# ScanMasterVCI.net
KiCad netlist of a schematic drawn in EAGLE
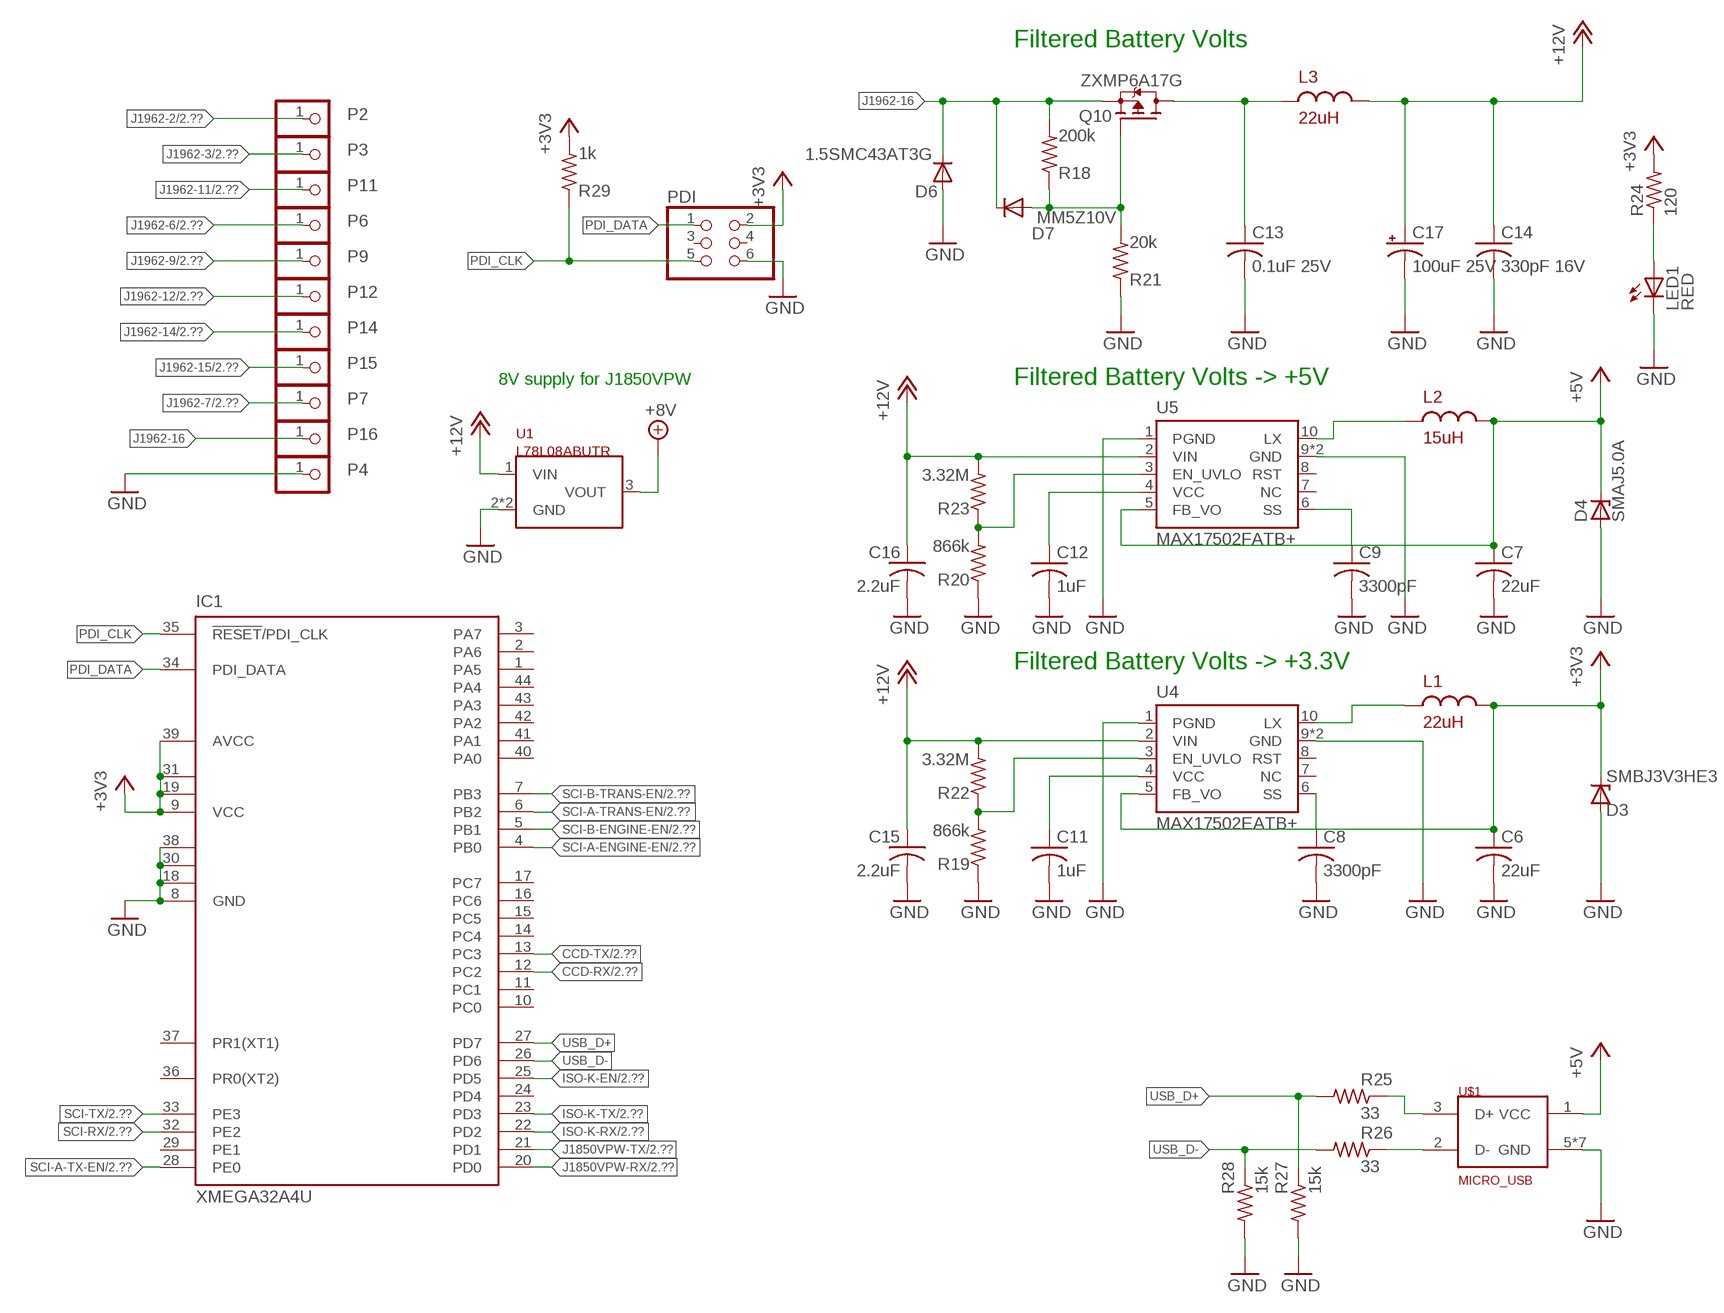
[diagram p0: schematic, sheet 1]
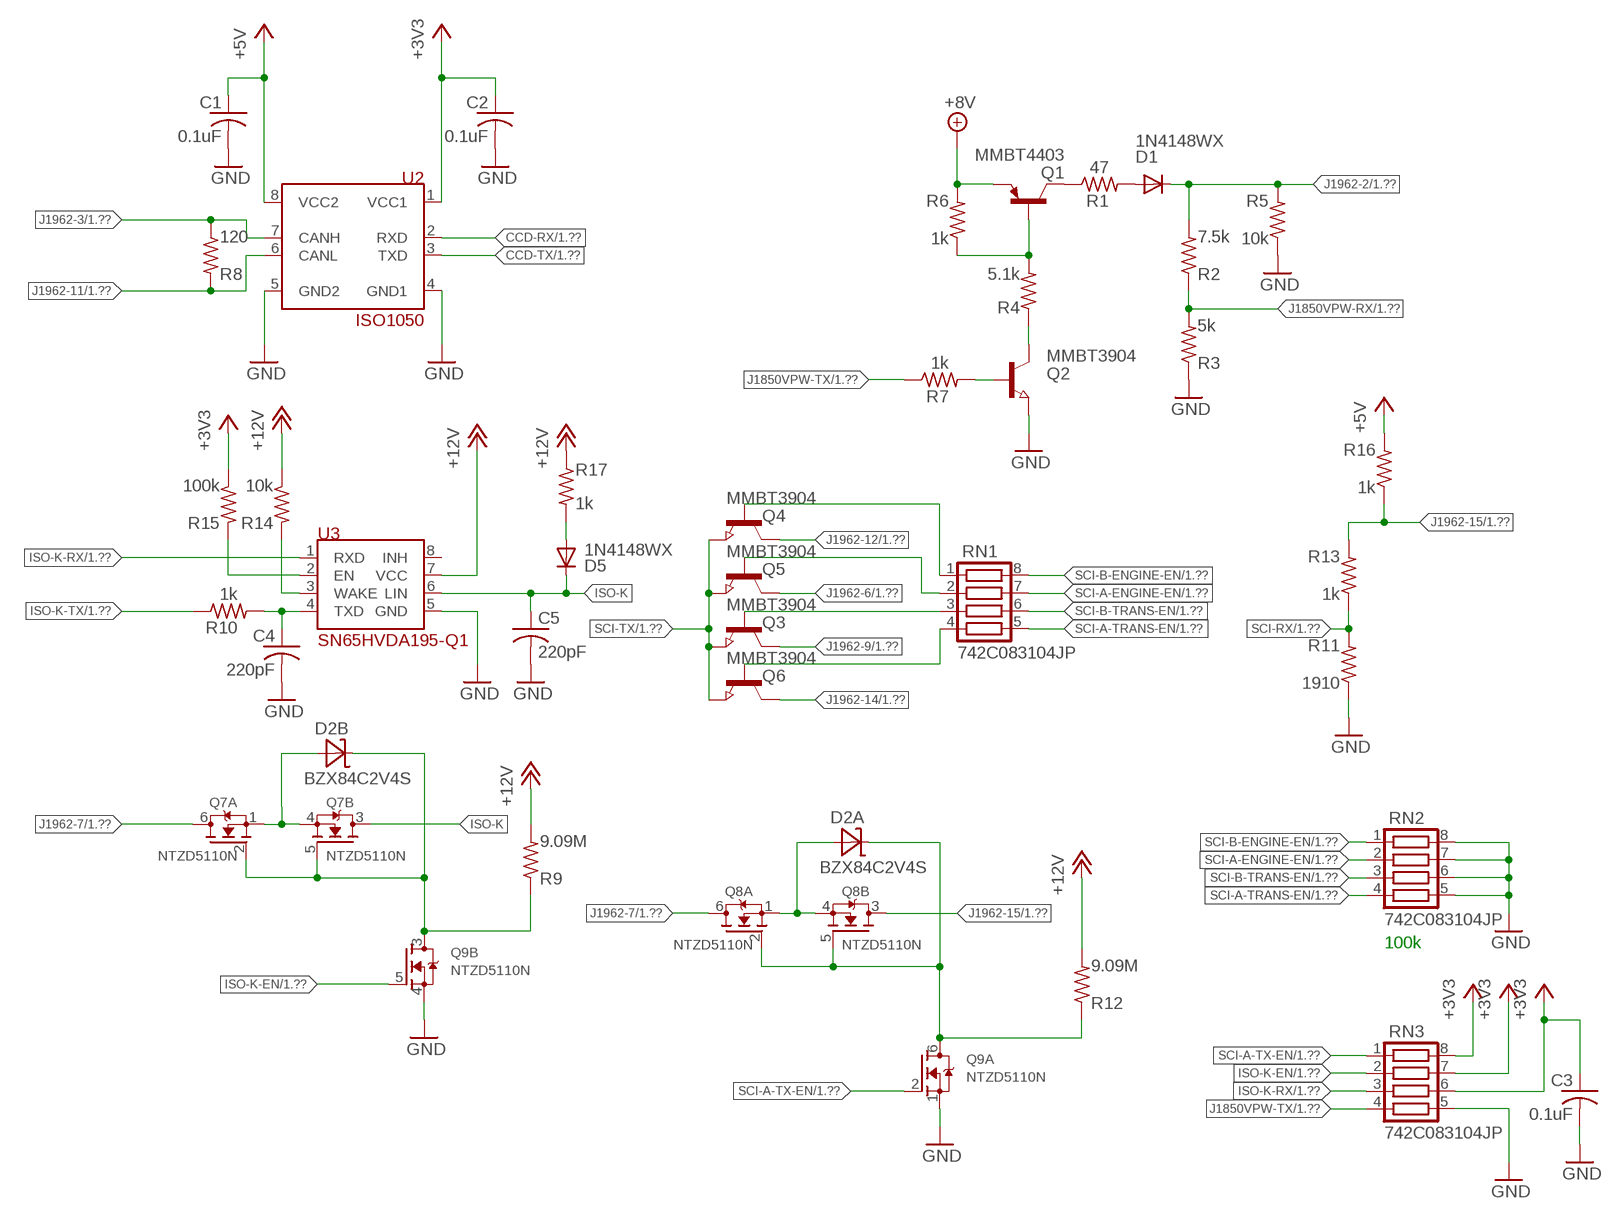
[diagram p1: schematic, sheet 2]

(export (version "E")
  (design (tool "Eeschema 10.0.6"))
  (components
    (comp (ref "C6")
      (value "22uF")
      (footprint "eagle-import:C0603")
      (libsource (lib "eagle-import") (part "C-USC0603"))
    )
    (comp (ref "C7")
      (value "22uF")
      (footprint "eagle-import:C0603")
      (libsource (lib "eagle-import") (part "C-USC0603"))
    )
    (comp (ref "C8")
      (value "3300pF")
      (footprint "eagle-import:C0603")
      (libsource (lib "eagle-import") (part "C-USC0603"))
    )
    (comp (ref "C9")
      (value "3300pF")
      (footprint "eagle-import:C0603")
      (libsource (lib "eagle-import") (part "C-USC0603"))
    )
    (comp (ref "C11")
      (value "1uF")
      (footprint "eagle-import:C0603")
      (libsource (lib "eagle-import") (part "C-USC0603"))
    )
    (comp (ref "C12")
      (value "1uF")
      (footprint "eagle-import:C0603")
      (libsource (lib "eagle-import") (part "C-USC0603"))
    )
    (comp (ref "C13")
      (value "0.1uF 25V")
      (footprint "eagle-import:C0603")
      (libsource (lib "eagle-import") (part "C-USC0603"))
    )
    (comp (ref "C14")
      (value "330pF 16V")
      (footprint "eagle-import:C0603")
      (libsource (lib "eagle-import") (part "C-USC0603"))
    )
    (comp (ref "C15")
      (value "2.2uF")
      (footprint "eagle-import:C0603")
      (libsource (lib "eagle-import") (part "C-USC0603"))
    )
    (comp (ref "C16")
      (value "2.2uF")
      (footprint "eagle-import:C0603")
      (libsource (lib "eagle-import") (part "C-USC0603"))
    )
    (comp (ref "C17")
      (value "100uF 25V")
      (footprint "eagle-import:CPOL-RADIAL-2.5MM-6.5MM")
      (libsource (lib "eagle-import") (part "100UF-POLAR-RADIAL-2.5MM-25V-20%"))
    )
    (comp (ref "D3")
      (value "SMBJ3V3HE3")
      (footprint "eagle-import:SMB")
      (libsource (lib "eagle-import") (part "ZENER-DIODESMB"))
    )
    (comp (ref "D4")
      (value "SMAJ5.0A")
      (footprint "eagle-import:SMB")
      (libsource (lib "eagle-import") (part "ZENER-DIODESMB"))
    )
    (comp (ref "D6")
      (value "1.5SMC43AT3G")
      (footprint "eagle-import:SMC")
      (libsource (lib "eagle-import") (part "DIODE-SMC"))
    )
    (comp (ref "D7")
      (value "MM5Z10V")
      (footprint "eagle-import:SOD523")
      (libsource (lib "eagle-import") (part "DIODE-SOD523"))
    )
    (comp (ref "IC1")
      (value "XMEGA32A4U")
      (footprint "eagle-import:TQFP44")
      (libsource (lib "eagle-import") (part "XMEGA16A4A"))
    )
    (comp (ref "L1")
      (value "22uH")
      (footprint "eagle-import:L0603")
      (libsource (lib "eagle-import") (part "INDUCTOR"))
    )
    (comp (ref "L2")
      (value "15uH")
      (footprint "eagle-import:L0603")
      (libsource (lib "eagle-import") (part "INDUCTOR"))
    )
    (comp (ref "L3")
      (value "22uH")
      (footprint "eagle-import:L0603")
      (libsource (lib "eagle-import") (part "INDUCTOR"))
    )
    (comp (ref "LED1")
      (value "RED")
      (footprint "eagle-import:CHIP-LED0603")
      (libsource (lib "eagle-import") (part "LEDCHIP-LED0603"))
    )
    (comp (ref "P2")
      (value "PINHD-1X1")
      (footprint "eagle-import:1X01")
      (libsource (lib "eagle-import") (part "PINHD-1X1"))
    )
    (comp (ref "P3")
      (value "PINHD-1X1")
      (footprint "eagle-import:1X01")
      (libsource (lib "eagle-import") (part "PINHD-1X1"))
    )
    (comp (ref "P4")
      (value "PINHD-1X1")
      (footprint "eagle-import:1X01")
      (libsource (lib "eagle-import") (part "PINHD-1X1"))
    )
    (comp (ref "P6")
      (value "PINHD-1X1")
      (footprint "eagle-import:1X01")
      (libsource (lib "eagle-import") (part "PINHD-1X1"))
    )
    (comp (ref "P7")
      (value "PINHD-1X1")
      (footprint "eagle-import:1X01")
      (libsource (lib "eagle-import") (part "PINHD-1X1"))
    )
    (comp (ref "P9")
      (value "PINHD-1X1")
      (footprint "eagle-import:1X01")
      (libsource (lib "eagle-import") (part "PINHD-1X1"))
    )
    (comp (ref "P11")
      (value "PINHD-1X1")
      (footprint "eagle-import:1X01")
      (libsource (lib "eagle-import") (part "PINHD-1X1"))
    )
    (comp (ref "P12")
      (value "PINHD-1X1")
      (footprint "eagle-import:1X01")
      (libsource (lib "eagle-import") (part "PINHD-1X1"))
    )
    (comp (ref "P14")
      (value "PINHD-1X1")
      (footprint "eagle-import:1X01")
      (libsource (lib "eagle-import") (part "PINHD-1X1"))
    )
    (comp (ref "P15")
      (value "PINHD-1X1")
      (footprint "eagle-import:1X01")
      (libsource (lib "eagle-import") (part "PINHD-1X1"))
    )
    (comp (ref "P16")
      (value "PINHD-1X1")
      (footprint "eagle-import:1X01")
      (libsource (lib "eagle-import") (part "PINHD-1X1"))
    )
    (comp (ref "PDI")
      (value "PINHD-2X3")
      (footprint "eagle-import:2X03")
      (libsource (lib "eagle-import") (part "PINHD-2X3"))
    )
    (comp (ref "Q10")
      (value "ZXMP6A17G")
      (footprint "eagle-import:SOT223")
      (libsource (lib "eagle-import") (part "ZXMP6A17G"))
    )
    (comp (ref "R18")
      (value "200k")
      (footprint "eagle-import:R0603")
      (libsource (lib "eagle-import") (part "R-US_R0603"))
    )
    (comp (ref "R19")
      (value "866k")
      (footprint "eagle-import:R0603")
      (libsource (lib "eagle-import") (part "R-US_R0603"))
    )
    (comp (ref "R20")
      (value "866k")
      (footprint "eagle-import:R0603")
      (libsource (lib "eagle-import") (part "R-US_R0603"))
    )
    (comp (ref "R21")
      (value "20k")
      (footprint "eagle-import:R0603")
      (libsource (lib "eagle-import") (part "R-US_R0603"))
    )
    (comp (ref "R22")
      (value "3.32M")
      (footprint "eagle-import:R0603")
      (libsource (lib "eagle-import") (part "R-US_R0603"))
    )
    (comp (ref "R23")
      (value "3.32M")
      (footprint "eagle-import:R0603")
      (libsource (lib "eagle-import") (part "R-US_R0603"))
    )
    (comp (ref "R24")
      (value "120")
      (footprint "eagle-import:R0603")
      (libsource (lib "eagle-import") (part "resistor_348_R-US_R0603"))
    )
    (comp (ref "R25")
      (value "33")
      (footprint "eagle-import:R0603")
      (libsource (lib "eagle-import") (part "R-US_R0603"))
    )
    (comp (ref "R26")
      (value "33")
      (footprint "eagle-import:R0603")
      (libsource (lib "eagle-import") (part "R-US_R0603"))
    )
    (comp (ref "R27")
      (value "15k")
      (footprint "eagle-import:R0603")
      (libsource (lib "eagle-import") (part "R-US_R0603"))
    )
    (comp (ref "R28")
      (value "15k")
      (footprint "eagle-import:R0603")
      (libsource (lib "eagle-import") (part "R-US_R0603"))
    )
    (comp (ref "R29")
      (value "1k")
      (footprint "eagle-import:R0603")
      (libsource (lib "eagle-import") (part "R-US_R0603"))
    )
    (comp (ref "U$1")
      (value "MICRO_USB")
      (footprint "eagle-import:10118192")
      (libsource (lib "eagle-import") (part "MICRO_USB"))
    )
    (comp (ref "U1")
      (value "L78L08ABUTR")
      (footprint "eagle-import:SOT89")
      (libsource (lib "eagle-import") (part "L78L"))
    )
    (comp (ref "U4")
      (value "MAX17502EATB+")
      (footprint "eagle-import:TDFN-10-EP")
      (libsource (lib "eagle-import") (part "MAX17502"))
    )
    (comp (ref "U5")
      (value "MAX17502FATB+")
      (footprint "eagle-import:TDFN-10-EP")
      (libsource (lib "eagle-import") (part "MAX17502"))
    )
    (comp (ref "C1")
      (value "0.1uF")
      (footprint "eagle-import:C0603")
      (libsource (lib "eagle-import") (part "C-USC0603"))
    )
    (comp (ref "C2")
      (value "0.1uF")
      (footprint "eagle-import:C0603")
      (libsource (lib "eagle-import") (part "C-USC0603"))
    )
    (comp (ref "C3")
      (value "0.1uF")
      (footprint "eagle-import:C0603")
      (libsource (lib "eagle-import") (part "C-USC0603"))
    )
    (comp (ref "C4")
      (value "220pF")
      (footprint "eagle-import:C0603")
      (libsource (lib "eagle-import") (part "C-USC0603"))
    )
    (comp (ref "C5")
      (value "220pF")
      (footprint "eagle-import:C0603")
      (libsource (lib "eagle-import") (part "C-USC0603"))
    )
    (comp (ref "D1")
      (value "1N4148WX")
      (footprint "eagle-import:SOD323-R")
      (libsource (lib "eagle-import") (part "DIODE-SOD323-R"))
    )
    (comp (ref "D2")
      (value "BZX84C2V4S")
      (footprint "eagle-import:SOT363")
      (libsource (lib "eagle-import") (part "BZX84C2V4S"))
    )
    (comp (ref "D5")
      (value "1N4148WX")
      (footprint "eagle-import:SOD323-R")
      (libsource (lib "eagle-import") (part "DIODE-SOD323-R"))
    )
    (comp (ref "Q1")
      (value "MMBT4403")
      (footprint "eagle-import:SOT23-BEC")
      (libsource (lib "eagle-import") (part "MMBT4403SMDLT1"))
    )
    (comp (ref "Q2")
      (value "MMBT3904")
      (footprint "eagle-import:SOT23")
      (libsource (lib "eagle-import") (part "NPN-TRANSISTOR_SOT23"))
    )
    (comp (ref "Q3")
      (value "MMBT3904")
      (footprint "eagle-import:SOT23")
      (libsource (lib "eagle-import") (part "NPN-TRANSISTOR_SOT23"))
    )
    (comp (ref "Q4")
      (value "MMBT3904")
      (footprint "eagle-import:SOT23")
      (libsource (lib "eagle-import") (part "NPN-TRANSISTOR_SOT23"))
    )
    (comp (ref "Q5")
      (value "MMBT3904")
      (footprint "eagle-import:SOT23")
      (libsource (lib "eagle-import") (part "NPN-TRANSISTOR_SOT23"))
    )
    (comp (ref "Q6")
      (value "MMBT3904")
      (footprint "eagle-import:SOT23")
      (libsource (lib "eagle-import") (part "NPN-TRANSISTOR_SOT23"))
    )
    (comp (ref "Q7")
      (value "NTZD5110N")
      (footprint "eagle-import:SOT563")
      (libsource (lib "eagle-import") (part "NTZD5110N"))
    )
    (comp (ref "Q8")
      (value "NTZD5110N")
      (footprint "eagle-import:SOT563")
      (libsource (lib "eagle-import") (part "NTZD5110N"))
    )
    (comp (ref "Q9")
      (value "NTZD5110N")
      (footprint "eagle-import:SOT563")
      (libsource (lib "eagle-import") (part "NTZD5110N"))
    )
    (comp (ref "R1")
      (value "47")
      (footprint "eagle-import:R0603")
      (libsource (lib "eagle-import") (part "R-US_R0603"))
    )
    (comp (ref "R2")
      (value "7.5k")
      (footprint "eagle-import:R0603")
      (libsource (lib "eagle-import") (part "R-US_R0603"))
    )
    (comp (ref "R3")
      (value "5k")
      (footprint "eagle-import:R0603")
      (libsource (lib "eagle-import") (part "R-US_R0603"))
    )
    (comp (ref "R4")
      (value "5.1k")
      (footprint "eagle-import:R0603")
      (libsource (lib "eagle-import") (part "R-US_R0603"))
    )
    (comp (ref "R5")
      (value "10k")
      (footprint "eagle-import:R0603")
      (libsource (lib "eagle-import") (part "R-US_R0603"))
    )
    (comp (ref "R6")
      (value "1k")
      (footprint "eagle-import:R0603")
      (libsource (lib "eagle-import") (part "R-US_R0603"))
    )
    (comp (ref "R7")
      (value "1k")
      (footprint "eagle-import:R0603")
      (libsource (lib "eagle-import") (part "R-US_R0603"))
    )
    (comp (ref "R8")
      (value "120")
      (footprint "eagle-import:R0603")
      (libsource (lib "eagle-import") (part "R-US_R0603"))
    )
    (comp (ref "R9")
      (value "9.09M")
      (footprint "eagle-import:R0603")
      (libsource (lib "eagle-import") (part "R-US_R0603"))
    )
    (comp (ref "R10")
      (value "1k")
      (footprint "eagle-import:R0603")
      (libsource (lib "eagle-import") (part "R-US_R0603"))
    )
    (comp (ref "R11")
      (value "1910")
      (footprint "eagle-import:R0603")
      (libsource (lib "eagle-import") (part "R-US_R0603"))
    )
    (comp (ref "R12")
      (value "9.09M")
      (footprint "eagle-import:R0603")
      (libsource (lib "eagle-import") (part "R-US_R0603"))
    )
    (comp (ref "R13")
      (value "1k")
      (footprint "eagle-import:R0603")
      (libsource (lib "eagle-import") (part "R-US_R0603"))
    )
    (comp (ref "R14")
      (value "10k")
      (footprint "eagle-import:R0603")
      (libsource (lib "eagle-import") (part "R-US_R0603"))
    )
    (comp (ref "R15")
      (value "100k")
      (footprint "eagle-import:R0603")
      (libsource (lib "eagle-import") (part "R-US_R0603"))
    )
    (comp (ref "R16")
      (value "1k")
      (footprint "eagle-import:R0603")
      (libsource (lib "eagle-import") (part "R-US_R0603"))
    )
    (comp (ref "R17")
      (value "1k")
      (footprint "eagle-import:R0603")
      (libsource (lib "eagle-import") (part "R-US_R0603"))
    )
    (comp (ref "RN1")
      (value "742C083104JP")
      (footprint "eagle-import:CTS742C083")
      (libsource (lib "eagle-import") (part "CTS742C083"))
    )
    (comp (ref "RN2")
      (value "742C083104JP")
      (footprint "eagle-import:CTS742C083")
      (libsource (lib "eagle-import") (part "CTS742C083"))
    )
    (comp (ref "RN3")
      (value "742C083104JP")
      (footprint "eagle-import:CTS742C083")
      (libsource (lib "eagle-import") (part "CTS742C083"))
    )
    (comp (ref "U2")
      (value "ISO1050")
      (footprint "eagle-import:SOP08")
      (libsource (lib "eagle-import") (part "ISO1050"))
    )
    (comp (ref "U3")
      (value "SN65HVDA195-Q1")
      (footprint "eagle-import:SO08")
      (libsource (lib "eagle-import") (part "SN65HVDA195-Q1"))
    )
  )
  (nets
    (net (code "1") (name "+3V3") (class "Default")
      (node (ref "C2") (pin "1") (pinfunction "1_1") (pintype "passive"))
      (node (ref "C3") (pin "1") (pinfunction "1_1") (pintype "passive"))
      (node (ref "C6") (pin "1") (pinfunction "1_1") (pintype "passive"))
      (node (ref "D3") (pin "C") (pinfunction "C_C") (pintype "passive"))
      (node (ref "IC1") (pin "19") (pinfunction "VCC1_19") (pintype "power_in"))
      (node (ref "IC1") (pin "31") (pinfunction "VCC2_31") (pintype "power_in"))
      (node (ref "IC1") (pin "39") (pinfunction "AVCC_39") (pintype "power_in"))
      (node (ref "IC1") (pin "9") (pinfunction "VCC_9") (pintype "power_in"))
      (node (ref "L1") (pin "2") (pinfunction "2_2") (pintype "passive"))
      (node (ref "PDI") (pin "2") (pinfunction "2_2") (pintype "passive"))
      (node (ref "R15") (pin "1") (pinfunction "1_1") (pintype "passive"))
      (node (ref "R24") (pin "2") (pinfunction "2_2") (pintype "passive"))
      (node (ref "R29") (pin "2") (pinfunction "2_2") (pintype "passive"))
      (node (ref "RN3") (pin "6") (pinfunction "6_6") (pintype "passive"))
      (node (ref "RN3") (pin "7") (pinfunction "7_7") (pintype "passive"))
      (node (ref "RN3") (pin "8") (pinfunction "8_8") (pintype "passive"))
      (node (ref "U2") (pin "1") (pinfunction "VCC1_1") (pintype "power_in"))
      (node (ref "U4") (pin "5") (pinfunction "FB_VO_5") (pintype "input"))
    )
    (net (code "2") (name "+5V") (class "Default")
      (node (ref "C1") (pin "1") (pinfunction "1_1") (pintype "passive"))
      (node (ref "C7") (pin "1") (pinfunction "1_1") (pintype "passive"))
      (node (ref "D4") (pin "C") (pinfunction "C_C") (pintype "passive"))
      (node (ref "L2") (pin "2") (pinfunction "2_2") (pintype "passive"))
      (node (ref "R16") (pin "2") (pinfunction "2_2") (pintype "passive"))
      (node (ref "U$1") (pin "1") (pinfunction "VCC_1") (pintype "power_in"))
      (node (ref "U2") (pin "8") (pinfunction "VCC2_8") (pintype "power_in"))
      (node (ref "U5") (pin "5") (pinfunction "FB_VO_5") (pintype "input"))
    )
    (net (code "3") (name "+8V") (class "Default")
      (node (ref "Q1") (pin "E") (pinfunction "E_E") (pintype "passive"))
      (node (ref "R6") (pin "2") (pinfunction "2_2") (pintype "passive"))
      (node (ref "U1") (pin "3") (pinfunction "VOUT_3") (pintype "power_in"))
    )
    (net (code "4") (name "+12V") (class "Default")
      (node (ref "C14") (pin "1") (pinfunction "1_1") (pintype "passive"))
      (node (ref "C15") (pin "1") (pinfunction "1_1") (pintype "passive"))
      (node (ref "C16") (pin "1") (pinfunction "1_1") (pintype "passive"))
      (node (ref "C17") (pin "1") (pinfunction "+_1") (pintype "passive"))
      (node (ref "L3") (pin "2") (pinfunction "2_2") (pintype "passive"))
      (node (ref "R12") (pin "2") (pinfunction "2_2") (pintype "passive"))
      (node (ref "R14") (pin "1") (pinfunction "1_1") (pintype "passive"))
      (node (ref "R17") (pin "1") (pinfunction "1_1") (pintype "passive"))
      (node (ref "R22") (pin "2") (pinfunction "2_2") (pintype "passive"))
      (node (ref "R23") (pin "2") (pinfunction "2_2") (pintype "passive"))
      (node (ref "R9") (pin "2") (pinfunction "2_2") (pintype "passive"))
      (node (ref "U1") (pin "1") (pinfunction "VIN_1") (pintype "power_in"))
      (node (ref "U3") (pin "7") (pinfunction "VCC_7") (pintype "power_in"))
      (node (ref "U4") (pin "2") (pinfunction "VIN_2") (pintype "power_in"))
      (node (ref "U5") (pin "2") (pinfunction "VIN_2") (pintype "power_in"))
    )
    (net (code "5") (name "CCD-RX") (class "Default")
      (node (ref "IC1") (pin "12") (pinfunction "PC2_12") (pintype "bidirectional"))
      (node (ref "U2") (pin "2") (pinfunction "RXD_2") (pintype "output"))
    )
    (net (code "6") (name "CCD-TX") (class "Default")
      (node (ref "IC1") (pin "13") (pinfunction "PC3_13") (pintype "bidirectional"))
      (node (ref "U2") (pin "3") (pinfunction "TXD_3") (pintype "input"))
    )
    (net (code "7") (name "GND") (class "Default")
      (node (ref "C1") (pin "2") (pinfunction "2_2") (pintype "passive"))
      (node (ref "C11") (pin "2") (pinfunction "2_2") (pintype "passive"))
      (node (ref "C12") (pin "2") (pinfunction "2_2") (pintype "passive"))
      (node (ref "C13") (pin "2") (pinfunction "2_2") (pintype "passive"))
      (node (ref "C14") (pin "2") (pinfunction "2_2") (pintype "passive"))
      (node (ref "C15") (pin "2") (pinfunction "2_2") (pintype "passive"))
      (node (ref "C16") (pin "2") (pinfunction "2_2") (pintype "passive"))
      (node (ref "C17") (pin "2") (pinfunction "-_2") (pintype "passive"))
      (node (ref "C2") (pin "2") (pinfunction "2_2") (pintype "passive"))
      (node (ref "C3") (pin "2") (pinfunction "2_2") (pintype "passive"))
      (node (ref "C4") (pin "2") (pinfunction "2_2") (pintype "passive"))
      (node (ref "C5") (pin "2") (pinfunction "2_2") (pintype "passive"))
      (node (ref "C6") (pin "2") (pinfunction "2_2") (pintype "passive"))
      (node (ref "C7") (pin "2") (pinfunction "2_2") (pintype "passive"))
      (node (ref "C8") (pin "2") (pinfunction "2_2") (pintype "passive"))
      (node (ref "C9") (pin "2") (pinfunction "2_2") (pintype "passive"))
      (node (ref "D3") (pin "A") (pinfunction "A_A") (pintype "passive"))
      (node (ref "D4") (pin "A") (pinfunction "A_A") (pintype "passive"))
      (node (ref "D6") (pin "A") (pinfunction "A_A") (pintype "passive"))
      (node (ref "IC1") (pin "18") (pinfunction "GND1_18") (pintype "power_in"))
      (node (ref "IC1") (pin "30") (pinfunction "GND2_30") (pintype "power_in"))
      (node (ref "IC1") (pin "38") (pinfunction "GND3_38") (pintype "power_in"))
      (node (ref "IC1") (pin "8") (pinfunction "GND_8") (pintype "power_in"))
      (node (ref "LED1") (pin "C") (pinfunction "C_C") (pintype "passive"))
      (node (ref "P4") (pin "1") (pinfunction "1_1") (pintype "passive"))
      (node (ref "PDI") (pin "6") (pinfunction "6_6") (pintype "passive"))
      (node (ref "Q2") (pin "2") (pinfunction "E_2") (pintype "passive"))
      (node (ref "Q9") (pin "1") (pinfunction "S_1") (pintype "passive"))
      (node (ref "Q9") (pin "4") (pinfunction "S_4") (pintype "passive"))
      (node (ref "R11") (pin "1") (pinfunction "1_1") (pintype "passive"))
      (node (ref "R19") (pin "1") (pinfunction "1_1") (pintype "passive"))
      (node (ref "R20") (pin "1") (pinfunction "1_1") (pintype "passive"))
      (node (ref "R21") (pin "1") (pinfunction "1_1") (pintype "passive"))
      (node (ref "R27") (pin "2") (pinfunction "2_2") (pintype "passive"))
      (node (ref "R28") (pin "2") (pinfunction "2_2") (pintype "passive"))
      (node (ref "R3") (pin "1") (pinfunction "1_1") (pintype "passive"))
      (node (ref "R5") (pin "1") (pinfunction "1_1") (pintype "passive"))
      (node (ref "RN2") (pin "5") (pinfunction "5_5") (pintype "passive"))
      (node (ref "RN2") (pin "6") (pinfunction "6_6") (pintype "passive"))
      (node (ref "RN2") (pin "7") (pinfunction "7_7") (pintype "passive"))
      (node (ref "RN2") (pin "8") (pinfunction "8_8") (pintype "passive"))
      (node (ref "RN3") (pin "5") (pinfunction "5_5") (pintype "passive"))
      (node (ref "U$1") (pin "5") (pinfunction "GND_5") (pintype "power_in"))
      (node (ref "U$1") (pin "M1") (pinfunction "GND_M1") (pintype "power_in"))
      (node (ref "U$1") (pin "M2") (pinfunction "GND_M2") (pintype "power_in"))
      (node (ref "U$1") (pin "M3") (pinfunction "GND_M3") (pintype "power_in"))
      (node (ref "U$1") (pin "M4") (pinfunction "GND_M4") (pintype "power_in"))
      (node (ref "U$1") (pin "M5") (pinfunction "GND_M5") (pintype "power_in"))
      (node (ref "U$1") (pin "M6") (pinfunction "GND_M6") (pintype "power_in"))
      (node (ref "U1") (pin "2") (pinfunction "GND_2") (pintype "power_in"))
      (node (ref "U1") (pin "2@1") (pinfunction "GND_2@1") (pintype "power_in"))
      (node (ref "U2") (pin "4") (pinfunction "GND1_4") (pintype "power_in"))
      (node (ref "U2") (pin "5") (pinfunction "GND2_5") (pintype "power_in"))
      (node (ref "U3") (pin "5") (pinfunction "GND_5") (pintype "power_in"))
      (node (ref "U4") (pin "1") (pinfunction "PGND_1") (pintype "power_in"))
      (node (ref "U4") (pin "9") (pinfunction "GND_9") (pintype "power_in"))
      (node (ref "U4") (pin "EPAD") (pinfunction "GND_EPAD") (pintype "power_in"))
      (node (ref "U5") (pin "1") (pinfunction "PGND_1") (pintype "power_in"))
      (node (ref "U5") (pin "9") (pinfunction "GND_9") (pintype "power_in"))
      (node (ref "U5") (pin "EPAD") (pinfunction "GND_EPAD") (pintype "power_in"))
    )
    (net (code "8") (name "ISO-K") (class "Default")
      (node (ref "C5") (pin "1") (pinfunction "1_1") (pintype "passive"))
      (node (ref "D5") (pin "C") (pinfunction "C_C") (pintype "passive"))
      (node (ref "Q7") (pin "3") (pinfunction "D_3") (pintype "passive"))
      (node (ref "U3") (pin "6") (pinfunction "LIN_6") (pintype "bidirectional"))
    )
    (net (code "9") (name "ISO-K-EN") (class "Default")
      (node (ref "IC1") (pin "25") (pinfunction "PD5_25") (pintype "bidirectional"))
      (node (ref "Q9") (pin "5") (pinfunction "G_5") (pintype "passive"))
      (node (ref "RN3") (pin "2") (pinfunction "2_2") (pintype "passive"))
    )
    (net (code "10") (name "ISO-K-RX") (class "Default")
      (node (ref "IC1") (pin "22") (pinfunction "PD2_22") (pintype "bidirectional"))
      (node (ref "RN3") (pin "3") (pinfunction "3_3") (pintype "passive"))
      (node (ref "U3") (pin "1") (pinfunction "RXD_1") (pintype "output"))
    )
    (net (code "11") (name "ISO-K-TX") (class "Default")
      (node (ref "IC1") (pin "23") (pinfunction "PD3_23") (pintype "bidirectional"))
      (node (ref "R10") (pin "1") (pinfunction "1_1") (pintype "passive"))
    )
    (net (code "12") (name "J1850VPW-RX") (class "Default")
      (node (ref "IC1") (pin "20") (pinfunction "PD0_20") (pintype "bidirectional"))
      (node (ref "R2") (pin "1") (pinfunction "1_1") (pintype "passive"))
      (node (ref "R3") (pin "2") (pinfunction "2_2") (pintype "passive"))
    )
    (net (code "13") (name "J1850VPW-TX") (class "Default")
      (node (ref "IC1") (pin "21") (pinfunction "PD1_21") (pintype "bidirectional"))
      (node (ref "R7") (pin "1") (pinfunction "1_1") (pintype "passive"))
      (node (ref "RN3") (pin "4") (pinfunction "4_4") (pintype "passive"))
    )
    (net (code "14") (name "J1962-2") (class "Default")
      (node (ref "D1") (pin "C") (pinfunction "C_C") (pintype "passive"))
      (node (ref "P2") (pin "1") (pinfunction "1_1") (pintype "passive"))
      (node (ref "R2") (pin "2") (pinfunction "2_2") (pintype "passive"))
      (node (ref "R5") (pin "2") (pinfunction "2_2") (pintype "passive"))
    )
    (net (code "15") (name "J1962-3") (class "Default")
      (node (ref "P3") (pin "1") (pinfunction "1_1") (pintype "passive"))
      (node (ref "R8") (pin "1") (pinfunction "1_1") (pintype "passive"))
      (node (ref "U2") (pin "7") (pinfunction "CANH_7") (pintype "input"))
    )
    (net (code "16") (name "J1962-6") (class "Default")
      (node (ref "P6") (pin "1") (pinfunction "1_1") (pintype "passive"))
      (node (ref "Q5") (pin "3") (pinfunction "C_3") (pintype "passive"))
    )
    (net (code "17") (name "J1962-7") (class "Default")
      (node (ref "P7") (pin "1") (pinfunction "1_1") (pintype "passive"))
      (node (ref "Q7") (pin "6") (pinfunction "D_6") (pintype "passive"))
      (node (ref "Q8") (pin "6") (pinfunction "D_6") (pintype "passive"))
    )
    (net (code "18") (name "J1962-9") (class "Default")
      (node (ref "P9") (pin "1") (pinfunction "1_1") (pintype "passive"))
      (node (ref "Q3") (pin "3") (pinfunction "C_3") (pintype "passive"))
    )
    (net (code "19") (name "J1962-11") (class "Default")
      (node (ref "P11") (pin "1") (pinfunction "1_1") (pintype "passive"))
      (node (ref "R8") (pin "2") (pinfunction "2_2") (pintype "passive"))
      (node (ref "U2") (pin "6") (pinfunction "CANL_6") (pintype "input"))
    )
    (net (code "20") (name "J1962-12") (class "Default")
      (node (ref "P12") (pin "1") (pinfunction "1_1") (pintype "passive"))
      (node (ref "Q4") (pin "3") (pinfunction "C_3") (pintype "passive"))
    )
    (net (code "21") (name "J1962-14") (class "Default")
      (node (ref "P14") (pin "1") (pinfunction "1_1") (pintype "passive"))
      (node (ref "Q6") (pin "3") (pinfunction "C_3") (pintype "passive"))
    )
    (net (code "22") (name "J1962-15") (class "Default")
      (node (ref "P15") (pin "1") (pinfunction "1_1") (pintype "passive"))
      (node (ref "Q8") (pin "3") (pinfunction "D_3") (pintype "passive"))
      (node (ref "R13") (pin "2") (pinfunction "2_2") (pintype "passive"))
      (node (ref "R16") (pin "1") (pinfunction "1_1") (pintype "passive"))
    )
    (net (code "23") (name "J1962-16") (class "Default")
      (node (ref "D6") (pin "C") (pinfunction "C_C") (pintype "passive"))
      (node (ref "D7") (pin "C") (pinfunction "C_C") (pintype "passive"))
      (node (ref "P16") (pin "1") (pinfunction "1_1") (pintype "passive"))
      (node (ref "Q10") (pin "3") (pinfunction "S_3") (pintype "passive"))
      (node (ref "R18") (pin "2") (pinfunction "2_2") (pintype "passive"))
    )
    (net (code "24") (name "Net-(C13-Pad1)") (class "Default")
      (node (ref "C13") (pin "1") (pinfunction "1_1") (pintype "passive"))
      (node (ref "L3") (pin "1") (pinfunction "1_1") (pintype "passive"))
      (node (ref "Q10") (pin "2") (pinfunction "D_2") (pintype "passive"))
      (node (ref "Q10") (pin "4") (pinfunction "D_4") (pintype "passive"))
    )
    (net (code "25") (name "Net-(D1-PadA)") (class "Default")
      (node (ref "D1") (pin "A") (pinfunction "A_A") (pintype "passive"))
      (node (ref "R1") (pin "2") (pinfunction "2_2") (pintype "passive"))
    )
    (net (code "26") (name "Net-(D2A-A)") (class "Default")
      (node (ref "D2") (pin "2") (pinfunction "A_2") (pintype "passive"))
      (node (ref "Q8") (pin "1") (pinfunction "S_1") (pintype "passive"))
      (node (ref "Q8") (pin "4") (pinfunction "S_4") (pintype "passive"))
    )
    (net (code "27") (name "Net-(D2A-C)") (class "Default")
      (node (ref "D2") (pin "3") (pinfunction "C_3") (pintype "passive"))
      (node (ref "Q8") (pin "2") (pinfunction "G_2") (pintype "passive"))
      (node (ref "Q8") (pin "5") (pinfunction "G_5") (pintype "passive"))
      (node (ref "Q9") (pin "6") (pinfunction "D_6") (pintype "passive"))
      (node (ref "R12") (pin "1") (pinfunction "1_1") (pintype "passive"))
    )
    (net (code "28") (name "Net-(D2B-A)") (class "Default")
      (node (ref "D2") (pin "5") (pinfunction "A_5") (pintype "passive"))
      (node (ref "Q7") (pin "1") (pinfunction "S_1") (pintype "passive"))
      (node (ref "Q7") (pin "4") (pinfunction "S_4") (pintype "passive"))
    )
    (net (code "29") (name "Net-(D2B-C)") (class "Default")
      (node (ref "D2") (pin "6") (pinfunction "C_6") (pintype "passive"))
      (node (ref "Q7") (pin "2") (pinfunction "G_2") (pintype "passive"))
      (node (ref "Q7") (pin "5") (pinfunction "G_5") (pintype "passive"))
      (node (ref "Q9") (pin "3") (pinfunction "D_3") (pintype "passive"))
      (node (ref "R9") (pin "1") (pinfunction "1_1") (pintype "passive"))
    )
    (net (code "30") (name "Net-(D5-PadA)") (class "Default")
      (node (ref "D5") (pin "A") (pinfunction "A_A") (pintype "passive"))
      (node (ref "R17") (pin "2") (pinfunction "2_2") (pintype "passive"))
    )
    (net (code "31") (name "Net-(LED1-PadA)") (class "Default")
      (node (ref "LED1") (pin "A") (pinfunction "A_A") (pintype "passive"))
      (node (ref "R24") (pin "1") (pinfunction "1_1") (pintype "passive"))
    )
    (net (code "32") (name "Net-(Q1-PadB)") (class "Default")
      (node (ref "Q1") (pin "B") (pinfunction "B_B") (pintype "passive"))
      (node (ref "R4") (pin "2") (pinfunction "2_2") (pintype "passive"))
      (node (ref "R6") (pin "1") (pinfunction "1_1") (pintype "passive"))
    )
    (net (code "33") (name "Net-(Q1-PadC)") (class "Default")
      (node (ref "Q1") (pin "C") (pinfunction "C_C") (pintype "passive"))
      (node (ref "R1") (pin "1") (pinfunction "1_1") (pintype "passive"))
    )
    (net (code "34") (name "Net-(Q2-B)") (class "Default")
      (node (ref "Q2") (pin "1") (pinfunction "B_1") (pintype "passive"))
      (node (ref "R7") (pin "2") (pinfunction "2_2") (pintype "passive"))
    )
    (net (code "35") (name "Net-(Q2-C)") (class "Default")
      (node (ref "Q2") (pin "3") (pinfunction "C_3") (pintype "passive"))
      (node (ref "R4") (pin "1") (pinfunction "1_1") (pintype "passive"))
    )
    (net (code "36") (name "Net-(Q3-B)") (class "Default")
      (node (ref "Q3") (pin "1") (pinfunction "B_1") (pintype "passive"))
      (node (ref "RN1") (pin "3") (pinfunction "3_3") (pintype "passive"))
    )
    (net (code "37") (name "Net-(Q4-B)") (class "Default")
      (node (ref "Q4") (pin "1") (pinfunction "B_1") (pintype "passive"))
      (node (ref "RN1") (pin "1") (pinfunction "1_1") (pintype "passive"))
    )
    (net (code "38") (name "Net-(Q5-B)") (class "Default")
      (node (ref "Q5") (pin "1") (pinfunction "B_1") (pintype "passive"))
      (node (ref "RN1") (pin "2") (pinfunction "2_2") (pintype "passive"))
    )
    (net (code "39") (name "Net-(Q6-B)") (class "Default")
      (node (ref "Q6") (pin "1") (pinfunction "B_1") (pintype "passive"))
      (node (ref "RN1") (pin "4") (pinfunction "4_4") (pintype "passive"))
    )
    (net (code "40") (name "Net-(Q10-G)") (class "Default")
      (node (ref "D7") (pin "A") (pinfunction "A_A") (pintype "passive"))
      (node (ref "Q10") (pin "1") (pinfunction "G_1") (pintype "passive"))
      (node (ref "R18") (pin "1") (pinfunction "1_1") (pintype "passive"))
      (node (ref "R21") (pin "2") (pinfunction "2_2") (pintype "passive"))
    )
    (net (code "41") (name "Net-(U$1-D+)") (class "Default")
      (node (ref "R25") (pin "1") (pinfunction "1_1") (pintype "passive"))
      (node (ref "U$1") (pin "3") (pinfunction "D+_3") (pintype "bidirectional"))
    )
    (net (code "42") (name "Net-(U$1-D-)") (class "Default")
      (node (ref "R26") (pin "1") (pinfunction "1_1") (pintype "passive"))
      (node (ref "U$1") (pin "2") (pinfunction "D-_2") (pintype "bidirectional"))
    )
    (net (code "43") (name "Net-(U3-EN)") (class "Default")
      (node (ref "R15") (pin "2") (pinfunction "2_2") (pintype "passive"))
      (node (ref "U3") (pin "2") (pinfunction "EN_2") (pintype "input"))
    )
    (net (code "44") (name "Net-(U3-TXD)") (class "Default")
      (node (ref "C4") (pin "1") (pinfunction "1_1") (pintype "passive"))
      (node (ref "R10") (pin "2") (pinfunction "2_2") (pintype "passive"))
      (node (ref "U3") (pin "4") (pinfunction "TXD_4") (pintype "input"))
    )
    (net (code "45") (name "Net-(U3-WAKE)") (class "Default")
      (node (ref "R14") (pin "2") (pinfunction "2_2") (pintype "passive"))
      (node (ref "U3") (pin "3") (pinfunction "WAKE_3") (pintype "input"))
    )
    (net (code "46") (name "Net-(U4-EN_UVLO)") (class "Default")
      (node (ref "R19") (pin "2") (pinfunction "2_2") (pintype "passive"))
      (node (ref "R22") (pin "1") (pinfunction "1_1") (pintype "passive"))
      (node (ref "U4") (pin "3") (pinfunction "EN_UVLO_3") (pintype "input"))
    )
    (net (code "47") (name "Net-(U4-LX)") (class "Default")
      (node (ref "L1") (pin "1") (pinfunction "1_1") (pintype "passive"))
      (node (ref "U4") (pin "10") (pinfunction "LX_10") (pintype "power_in"))
    )
    (net (code "48") (name "Net-(U4-SS)") (class "Default")
      (node (ref "C8") (pin "1") (pinfunction "1_1") (pintype "passive"))
      (node (ref "U4") (pin "6") (pinfunction "SS_6") (pintype "input"))
    )
    (net (code "49") (name "Net-(U4-VCC)") (class "Default")
      (node (ref "C11") (pin "1") (pinfunction "1_1") (pintype "passive"))
      (node (ref "U4") (pin "4") (pinfunction "VCC_4") (pintype "power_in"))
    )
    (net (code "50") (name "Net-(U5-EN_UVLO)") (class "Default")
      (node (ref "R20") (pin "2") (pinfunction "2_2") (pintype "passive"))
      (node (ref "R23") (pin "1") (pinfunction "1_1") (pintype "passive"))
      (node (ref "U5") (pin "3") (pinfunction "EN_UVLO_3") (pintype "input"))
    )
    (net (code "51") (name "Net-(U5-LX)") (class "Default")
      (node (ref "L2") (pin "1") (pinfunction "1_1") (pintype "passive"))
      (node (ref "U5") (pin "10") (pinfunction "LX_10") (pintype "power_in"))
    )
    (net (code "52") (name "Net-(U5-SS)") (class "Default")
      (node (ref "C9") (pin "1") (pinfunction "1_1") (pintype "passive"))
      (node (ref "U5") (pin "6") (pinfunction "SS_6") (pintype "input"))
    )
    (net (code "53") (name "Net-(U5-VCC)") (class "Default")
      (node (ref "C12") (pin "1") (pinfunction "1_1") (pintype "passive"))
      (node (ref "U5") (pin "4") (pinfunction "VCC_4") (pintype "power_in"))
    )
    (net (code "54") (name "PDI_CLK") (class "Default")
      (node (ref "IC1") (pin "35") (pinfunction "~{RESET}/PDI_CLK_35") (pintype "bidirectional"))
      (node (ref "PDI") (pin "5") (pinfunction "5_5") (pintype "passive"))
      (node (ref "R29") (pin "1") (pinfunction "1_1") (pintype "passive"))
    )
    (net (code "55") (name "PDI_DATA") (class "Default")
      (node (ref "IC1") (pin "34") (pinfunction "PDI_DATA_34") (pintype "bidirectional"))
      (node (ref "PDI") (pin "1") (pinfunction "1_1") (pintype "passive"))
    )
    (net (code "56") (name "SCI-A-ENGINE-EN") (class "Default")
      (node (ref "IC1") (pin "4") (pinfunction "PB0_4") (pintype "bidirectional"))
      (node (ref "RN1") (pin "7") (pinfunction "7_7") (pintype "passive"))
      (node (ref "RN2") (pin "2") (pinfunction "2_2") (pintype "passive"))
    )
    (net (code "57") (name "SCI-A-TRANS-EN") (class "Default")
      (node (ref "IC1") (pin "6") (pinfunction "PB2_6") (pintype "bidirectional"))
      (node (ref "RN1") (pin "5") (pinfunction "5_5") (pintype "passive"))
      (node (ref "RN2") (pin "4") (pinfunction "4_4") (pintype "passive"))
    )
    (net (code "58") (name "SCI-A-TX-EN") (class "Default")
      (node (ref "IC1") (pin "28") (pinfunction "PE0_28") (pintype "bidirectional"))
      (node (ref "Q9") (pin "2") (pinfunction "G_2") (pintype "passive"))
      (node (ref "RN3") (pin "1") (pinfunction "1_1") (pintype "passive"))
    )
    (net (code "59") (name "SCI-B-ENGINE-EN") (class "Default")
      (node (ref "IC1") (pin "5") (pinfunction "PB1_5") (pintype "bidirectional"))
      (node (ref "RN1") (pin "8") (pinfunction "8_8") (pintype "passive"))
      (node (ref "RN2") (pin "1") (pinfunction "1_1") (pintype "passive"))
    )
    (net (code "60") (name "SCI-B-TRANS-EN") (class "Default")
      (node (ref "IC1") (pin "7") (pinfunction "PB3_7") (pintype "bidirectional"))
      (node (ref "RN1") (pin "6") (pinfunction "6_6") (pintype "passive"))
      (node (ref "RN2") (pin "3") (pinfunction "3_3") (pintype "passive"))
    )
    (net (code "61") (name "SCI-RX") (class "Default")
      (node (ref "IC1") (pin "32") (pinfunction "PE2_32") (pintype "bidirectional"))
      (node (ref "R11") (pin "2") (pinfunction "2_2") (pintype "passive"))
      (node (ref "R13") (pin "1") (pinfunction "1_1") (pintype "passive"))
    )
    (net (code "62") (name "SCI-TX") (class "Default")
      (node (ref "IC1") (pin "33") (pinfunction "PE3_33") (pintype "bidirectional"))
      (node (ref "Q3") (pin "2") (pinfunction "E_2") (pintype "passive"))
      (node (ref "Q4") (pin "2") (pinfunction "E_2") (pintype "passive"))
      (node (ref "Q5") (pin "2") (pinfunction "E_2") (pintype "passive"))
      (node (ref "Q6") (pin "2") (pinfunction "E_2") (pintype "passive"))
    )
    (net (code "63") (name "USB_D+") (class "Default")
      (node (ref "IC1") (pin "27") (pinfunction "PD7_27") (pintype "bidirectional"))
      (node (ref "R25") (pin "2") (pinfunction "2_2") (pintype "passive"))
      (node (ref "R27") (pin "1") (pinfunction "1_1") (pintype "passive"))
    )
    (net (code "64") (name "USB_D-") (class "Default")
      (node (ref "IC1") (pin "26") (pinfunction "PD6_26") (pintype "bidirectional"))
      (node (ref "R26") (pin "2") (pinfunction "2_2") (pintype "passive"))
      (node (ref "R28") (pin "1") (pinfunction "1_1") (pintype "passive"))
    )
    (net (code "65") (name "unconnected-(IC1-PA0-Pad40)") (class "Default")
      (node (ref "IC1") (pin "40") (pinfunction "PA0_40") (pintype "bidirectional"))
    )
    (net (code "66") (name "unconnected-(IC1-PA1-Pad41)") (class "Default")
      (node (ref "IC1") (pin "41") (pinfunction "PA1_41") (pintype "bidirectional"))
    )
    (net (code "67") (name "unconnected-(IC1-PA2-Pad42)") (class "Default")
      (node (ref "IC1") (pin "42") (pinfunction "PA2_42") (pintype "bidirectional"))
    )
    (net (code "68") (name "unconnected-(IC1-PA3-Pad43)") (class "Default")
      (node (ref "IC1") (pin "43") (pinfunction "PA3_43") (pintype "bidirectional"))
    )
    (net (code "69") (name "unconnected-(IC1-PA4-Pad44)") (class "Default")
      (node (ref "IC1") (pin "44") (pinfunction "PA4_44") (pintype "bidirectional"))
    )
    (net (code "70") (name "unconnected-(IC1-PA5-Pad1)") (class "Default")
      (node (ref "IC1") (pin "1") (pinfunction "PA5_1") (pintype "bidirectional"))
    )
    (net (code "71") (name "unconnected-(IC1-PA6-Pad2)") (class "Default")
      (node (ref "IC1") (pin "2") (pinfunction "PA6_2") (pintype "bidirectional"))
    )
    (net (code "72") (name "unconnected-(IC1-PA7-Pad3)") (class "Default")
      (node (ref "IC1") (pin "3") (pinfunction "PA7_3") (pintype "bidirectional"))
    )
    (net (code "73") (name "unconnected-(IC1-PC0-Pad10)") (class "Default")
      (node (ref "IC1") (pin "10") (pinfunction "PC0_10") (pintype "bidirectional"))
    )
    (net (code "74") (name "unconnected-(IC1-PC1-Pad11)") (class "Default")
      (node (ref "IC1") (pin "11") (pinfunction "PC1_11") (pintype "bidirectional"))
    )
    (net (code "75") (name "unconnected-(IC1-PC4-Pad14)") (class "Default")
      (node (ref "IC1") (pin "14") (pinfunction "PC4_14") (pintype "bidirectional"))
    )
    (net (code "76") (name "unconnected-(IC1-PC5-Pad15)") (class "Default")
      (node (ref "IC1") (pin "15") (pinfunction "PC5_15") (pintype "bidirectional"))
    )
    (net (code "77") (name "unconnected-(IC1-PC6-Pad16)") (class "Default")
      (node (ref "IC1") (pin "16") (pinfunction "PC6_16") (pintype "bidirectional"))
    )
    (net (code "78") (name "unconnected-(IC1-PC7-Pad17)") (class "Default")
      (node (ref "IC1") (pin "17") (pinfunction "PC7_17") (pintype "bidirectional"))
    )
    (net (code "79") (name "unconnected-(IC1-PD4-Pad24)") (class "Default")
      (node (ref "IC1") (pin "24") (pinfunction "PD4_24") (pintype "bidirectional"))
    )
    (net (code "80") (name "unconnected-(IC1-PE1-Pad29)") (class "Default")
      (node (ref "IC1") (pin "29") (pinfunction "PE1_29") (pintype "bidirectional"))
    )
    (net (code "81") (name "unconnected-(IC1-PR0(XT2)-Pad36)") (class "Default")
      (node (ref "IC1") (pin "36") (pinfunction "PR0(XT2)_36") (pintype "bidirectional"))
    )
    (net (code "82") (name "unconnected-(IC1-PR1(XT1)-Pad37)") (class "Default")
      (node (ref "IC1") (pin "37") (pinfunction "PR1(XT1)_37") (pintype "bidirectional"))
    )
    (net (code "83") (name "unconnected-(PDI-Pad3)") (class "Default")
      (node (ref "PDI") (pin "3") (pinfunction "3_3") (pintype "passive"))
    )
    (net (code "84") (name "unconnected-(PDI-Pad4)") (class "Default")
      (node (ref "PDI") (pin "4") (pinfunction "4_4") (pintype "passive"))
    )
    (net (code "85") (name "unconnected-(U3-INH-Pad8)") (class "Default")
      (node (ref "U3") (pin "8") (pinfunction "INH_8") (pintype "output"))
    )
    (net (code "86") (name "unconnected-(U4-NC-Pad7)") (class "Default")
      (node (ref "U4") (pin "7") (pinfunction "NC_7") (pintype "no_connect"))
    )
    (net (code "87") (name "unconnected-(U4-RST-Pad8)") (class "Default")
      (node (ref "U4") (pin "8") (pinfunction "RST_8") (pintype "output"))
    )
    (net (code "88") (name "unconnected-(U5-NC-Pad7)") (class "Default")
      (node (ref "U5") (pin "7") (pinfunction "NC_7") (pintype "no_connect"))
    )
    (net (code "89") (name "unconnected-(U5-RST-Pad8)") (class "Default")
      (node (ref "U5") (pin "8") (pinfunction "RST_8") (pintype "output"))
    )
  )
)
